# TSOP-II-44_v3_CY7C1021BV33.net
KiCad netlist of a schematic drawn in EAGLE
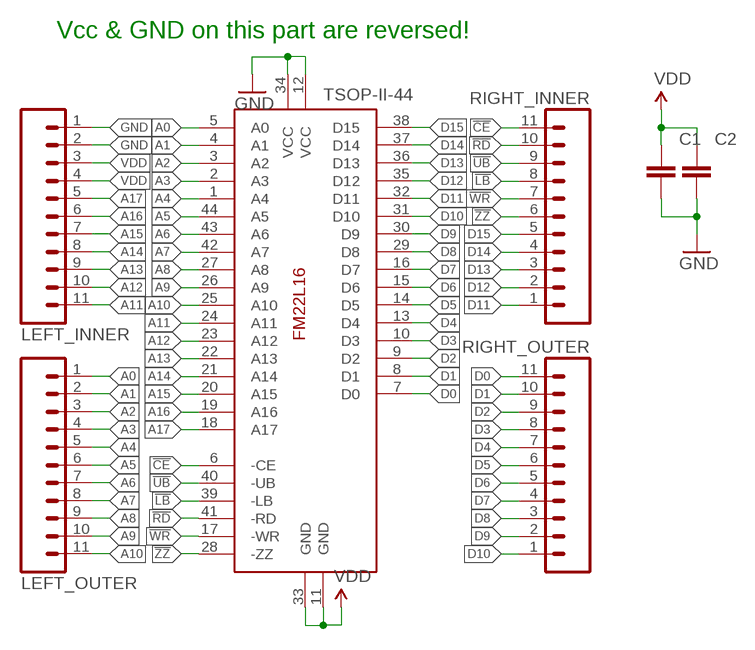
[diagram p0: schematic, sheet 1]

(export (version "E")
  (design (tool "Eeschema 10.0.6"))
  (components
    (comp (ref "C1")
      (value "CAPACITOR_NPOL-0603")
      (footprint "eagle-import:C603")
      (libsource (lib "eagle-import") (part "CAPACITOR_NPOL-0603"))
    )
    (comp (ref "C2")
      (value "CAPACITOR_NPOL-0603")
      (footprint "eagle-import:C603")
      (libsource (lib "eagle-import") (part "CAPACITOR_NPOL-0603"))
    )
    (comp (ref "LEFT_INNER")
      (value "M11PTH")
      (footprint "eagle-import:1X11")
      (libsource (lib "eagle-import") (part "M11PTH"))
    )
    (comp (ref "LEFT_OUTER")
      (value "M11PTH")
      (footprint "eagle-import:1X11")
      (libsource (lib "eagle-import") (part "M11PTH"))
    )
    (comp (ref "RIGHT_INNER")
      (value "M11PTH")
      (footprint "eagle-import:1X11")
      (libsource (lib "eagle-import") (part "M11PTH"))
    )
    (comp (ref "RIGHT_OUTER")
      (value "M11PTH")
      (footprint "eagle-import:1X11")
      (libsource (lib "eagle-import") (part "M11PTH"))
    )
    (comp (ref "TSOP-II-44")
      (value "FM22L16-TG")
      (footprint "eagle-import:TSOPII-44")
      (libsource (lib "eagle-import") (part "FM22L16-TG"))
    )
  )
  (nets
    (net (code "1") (name "/~{CE}") (class "Default")
      (node (ref "RIGHT_INNER") (pin "11") (pinfunction "11_11") (pintype "passive"))
      (node (ref "TSOP-II-44") (pin "6") (pinfunction "-CE_6") (pintype "input"))
    )
    (net (code "2") (name "/~{LB}") (class "Default")
      (node (ref "RIGHT_INNER") (pin "8") (pinfunction "8_8") (pintype "passive"))
      (node (ref "TSOP-II-44") (pin "39") (pinfunction "-LB_39") (pintype "input"))
    )
    (net (code "3") (name "/~{RD}") (class "Default")
      (node (ref "RIGHT_INNER") (pin "10") (pinfunction "10_10") (pintype "passive"))
      (node (ref "TSOP-II-44") (pin "41") (pinfunction "-RD_41") (pintype "input"))
    )
    (net (code "4") (name "/~{UB}") (class "Default")
      (node (ref "RIGHT_INNER") (pin "9") (pinfunction "9_9") (pintype "passive"))
      (node (ref "TSOP-II-44") (pin "40") (pinfunction "-UB_40") (pintype "input"))
    )
    (net (code "5") (name "/~{WR}") (class "Default")
      (node (ref "RIGHT_INNER") (pin "7") (pinfunction "7_7") (pintype "passive"))
      (node (ref "TSOP-II-44") (pin "17") (pinfunction "-WR_17") (pintype "input"))
    )
    (net (code "6") (name "/~{ZZ}") (class "Default")
      (node (ref "RIGHT_INNER") (pin "6") (pinfunction "6_6") (pintype "passive"))
      (node (ref "TSOP-II-44") (pin "28") (pinfunction "-ZZ_28") (pintype "input"))
    )
    (net (code "7") (name "A0") (class "Default")
      (node (ref "LEFT_OUTER") (pin "1") (pinfunction "1_1") (pintype "passive"))
      (node (ref "TSOP-II-44") (pin "5") (pinfunction "A0_5") (pintype "input"))
    )
    (net (code "8") (name "A1") (class "Default")
      (node (ref "LEFT_OUTER") (pin "2") (pinfunction "2_2") (pintype "passive"))
      (node (ref "TSOP-II-44") (pin "4") (pinfunction "A1_4") (pintype "input"))
    )
    (net (code "9") (name "A2") (class "Default")
      (node (ref "LEFT_OUTER") (pin "3") (pinfunction "3_3") (pintype "passive"))
      (node (ref "TSOP-II-44") (pin "3") (pinfunction "A2_3") (pintype "input"))
    )
    (net (code "10") (name "A3") (class "Default")
      (node (ref "LEFT_OUTER") (pin "4") (pinfunction "4_4") (pintype "passive"))
      (node (ref "TSOP-II-44") (pin "2") (pinfunction "A3_2") (pintype "input"))
    )
    (net (code "11") (name "A4") (class "Default")
      (node (ref "LEFT_OUTER") (pin "5") (pinfunction "5_5") (pintype "passive"))
      (node (ref "TSOP-II-44") (pin "1") (pinfunction "A4_1") (pintype "input"))
    )
    (net (code "12") (name "A5") (class "Default")
      (node (ref "LEFT_OUTER") (pin "6") (pinfunction "6_6") (pintype "passive"))
      (node (ref "TSOP-II-44") (pin "44") (pinfunction "A5_44") (pintype "input"))
    )
    (net (code "13") (name "A6") (class "Default")
      (node (ref "LEFT_OUTER") (pin "7") (pinfunction "7_7") (pintype "passive"))
      (node (ref "TSOP-II-44") (pin "43") (pinfunction "A6_43") (pintype "input"))
    )
    (net (code "14") (name "A7") (class "Default")
      (node (ref "LEFT_OUTER") (pin "8") (pinfunction "8_8") (pintype "passive"))
      (node (ref "TSOP-II-44") (pin "42") (pinfunction "A7_42") (pintype "input"))
    )
    (net (code "15") (name "A8") (class "Default")
      (node (ref "LEFT_OUTER") (pin "9") (pinfunction "9_9") (pintype "passive"))
      (node (ref "TSOP-II-44") (pin "27") (pinfunction "A8_27") (pintype "input"))
    )
    (net (code "16") (name "A9") (class "Default")
      (node (ref "LEFT_OUTER") (pin "10") (pinfunction "10_10") (pintype "passive"))
      (node (ref "TSOP-II-44") (pin "26") (pinfunction "A9_26") (pintype "input"))
    )
    (net (code "17") (name "A10") (class "Default")
      (node (ref "LEFT_OUTER") (pin "11") (pinfunction "11_11") (pintype "passive"))
      (node (ref "TSOP-II-44") (pin "25") (pinfunction "A10_25") (pintype "input"))
    )
    (net (code "18") (name "A11") (class "Default")
      (node (ref "LEFT_INNER") (pin "11") (pinfunction "11_11") (pintype "passive"))
      (node (ref "TSOP-II-44") (pin "24") (pinfunction "A11_24") (pintype "input"))
    )
    (net (code "19") (name "A12") (class "Default")
      (node (ref "LEFT_INNER") (pin "10") (pinfunction "10_10") (pintype "passive"))
      (node (ref "TSOP-II-44") (pin "23") (pinfunction "A12_23") (pintype "input"))
    )
    (net (code "20") (name "A13") (class "Default")
      (node (ref "LEFT_INNER") (pin "9") (pinfunction "9_9") (pintype "passive"))
      (node (ref "TSOP-II-44") (pin "22") (pinfunction "A13_22") (pintype "input"))
    )
    (net (code "21") (name "A14") (class "Default")
      (node (ref "LEFT_INNER") (pin "8") (pinfunction "8_8") (pintype "passive"))
      (node (ref "TSOP-II-44") (pin "21") (pinfunction "A14_21") (pintype "input"))
    )
    (net (code "22") (name "A15") (class "Default")
      (node (ref "LEFT_INNER") (pin "7") (pinfunction "7_7") (pintype "passive"))
      (node (ref "TSOP-II-44") (pin "20") (pinfunction "A15_20") (pintype "input"))
    )
    (net (code "23") (name "A16") (class "Default")
      (node (ref "LEFT_INNER") (pin "6") (pinfunction "6_6") (pintype "passive"))
      (node (ref "TSOP-II-44") (pin "19") (pinfunction "A16_19") (pintype "input"))
    )
    (net (code "24") (name "A17") (class "Default")
      (node (ref "LEFT_INNER") (pin "5") (pinfunction "5_5") (pintype "passive"))
      (node (ref "TSOP-II-44") (pin "18") (pinfunction "A17_18") (pintype "input"))
    )
    (net (code "25") (name "D0") (class "Default")
      (node (ref "RIGHT_OUTER") (pin "11") (pinfunction "11_11") (pintype "passive"))
      (node (ref "TSOP-II-44") (pin "7") (pinfunction "D0_7") (pintype "bidirectional"))
    )
    (net (code "26") (name "D1") (class "Default")
      (node (ref "RIGHT_OUTER") (pin "10") (pinfunction "10_10") (pintype "passive"))
      (node (ref "TSOP-II-44") (pin "8") (pinfunction "D1_8") (pintype "bidirectional"))
    )
    (net (code "27") (name "D2") (class "Default")
      (node (ref "RIGHT_OUTER") (pin "9") (pinfunction "9_9") (pintype "passive"))
      (node (ref "TSOP-II-44") (pin "9") (pinfunction "D2_9") (pintype "bidirectional"))
    )
    (net (code "28") (name "D3") (class "Default")
      (node (ref "RIGHT_OUTER") (pin "8") (pinfunction "8_8") (pintype "passive"))
      (node (ref "TSOP-II-44") (pin "10") (pinfunction "D3_10") (pintype "bidirectional"))
    )
    (net (code "29") (name "D4") (class "Default")
      (node (ref "RIGHT_OUTER") (pin "7") (pinfunction "7_7") (pintype "passive"))
      (node (ref "TSOP-II-44") (pin "13") (pinfunction "D4_13") (pintype "bidirectional"))
    )
    (net (code "30") (name "D5") (class "Default")
      (node (ref "RIGHT_OUTER") (pin "6") (pinfunction "6_6") (pintype "passive"))
      (node (ref "TSOP-II-44") (pin "14") (pinfunction "D5_14") (pintype "bidirectional"))
    )
    (net (code "31") (name "D6") (class "Default")
      (node (ref "RIGHT_OUTER") (pin "5") (pinfunction "5_5") (pintype "passive"))
      (node (ref "TSOP-II-44") (pin "15") (pinfunction "D6_15") (pintype "bidirectional"))
    )
    (net (code "32") (name "D7") (class "Default")
      (node (ref "RIGHT_OUTER") (pin "4") (pinfunction "4_4") (pintype "passive"))
      (node (ref "TSOP-II-44") (pin "16") (pinfunction "D7_16") (pintype "bidirectional"))
    )
    (net (code "33") (name "D8") (class "Default")
      (node (ref "RIGHT_OUTER") (pin "3") (pinfunction "3_3") (pintype "passive"))
      (node (ref "TSOP-II-44") (pin "29") (pinfunction "D8_29") (pintype "bidirectional"))
    )
    (net (code "34") (name "D9") (class "Default")
      (node (ref "RIGHT_OUTER") (pin "2") (pinfunction "2_2") (pintype "passive"))
      (node (ref "TSOP-II-44") (pin "30") (pinfunction "D9_30") (pintype "bidirectional"))
    )
    (net (code "35") (name "D10") (class "Default")
      (node (ref "RIGHT_OUTER") (pin "1") (pinfunction "1_1") (pintype "passive"))
      (node (ref "TSOP-II-44") (pin "31") (pinfunction "D10_31") (pintype "bidirectional"))
    )
    (net (code "36") (name "D11") (class "Default")
      (node (ref "RIGHT_INNER") (pin "1") (pinfunction "1_1") (pintype "passive"))
      (node (ref "TSOP-II-44") (pin "32") (pinfunction "D11_32") (pintype "bidirectional"))
    )
    (net (code "37") (name "D12") (class "Default")
      (node (ref "RIGHT_INNER") (pin "2") (pinfunction "2_2") (pintype "passive"))
      (node (ref "TSOP-II-44") (pin "35") (pinfunction "D12_35") (pintype "bidirectional"))
    )
    (net (code "38") (name "D13") (class "Default")
      (node (ref "RIGHT_INNER") (pin "3") (pinfunction "3_3") (pintype "passive"))
      (node (ref "TSOP-II-44") (pin "36") (pinfunction "D13_36") (pintype "bidirectional"))
    )
    (net (code "39") (name "D14") (class "Default")
      (node (ref "RIGHT_INNER") (pin "4") (pinfunction "4_4") (pintype "passive"))
      (node (ref "TSOP-II-44") (pin "37") (pinfunction "D14_37") (pintype "bidirectional"))
    )
    (net (code "40") (name "D15") (class "Default")
      (node (ref "RIGHT_INNER") (pin "5") (pinfunction "5_5") (pintype "passive"))
      (node (ref "TSOP-II-44") (pin "38") (pinfunction "D15_38") (pintype "bidirectional"))
    )
    (net (code "41") (name "GND") (class "Default")
      (node (ref "C1") (pin "2") (pinfunction "2_2") (pintype "passive"))
      (node (ref "C2") (pin "2") (pinfunction "2_2") (pintype "passive"))
      (node (ref "LEFT_INNER") (pin "1") (pinfunction "1_1") (pintype "passive"))
      (node (ref "LEFT_INNER") (pin "2") (pinfunction "2_2") (pintype "passive"))
      (node (ref "TSOP-II-44") (pin "12") (pinfunction "VCC_12") (pintype "power_in"))
      (node (ref "TSOP-II-44") (pin "34") (pinfunction "VCC_34") (pintype "power_in"))
    )
    (net (code "42") (name "VDD") (class "Default")
      (node (ref "C1") (pin "1") (pinfunction "1_1") (pintype "passive"))
      (node (ref "C2") (pin "1") (pinfunction "1_1") (pintype "passive"))
      (node (ref "LEFT_INNER") (pin "3") (pinfunction "3_3") (pintype "passive"))
      (node (ref "LEFT_INNER") (pin "4") (pinfunction "4_4") (pintype "passive"))
      (node (ref "TSOP-II-44") (pin "11") (pinfunction "GND_11") (pintype "power_in"))
      (node (ref "TSOP-II-44") (pin "33") (pinfunction "GND_33") (pintype "power_in"))
    )
  )
)
